# Motor_DC.net
KiCad netlist of a schematic drawn in Altium Designer
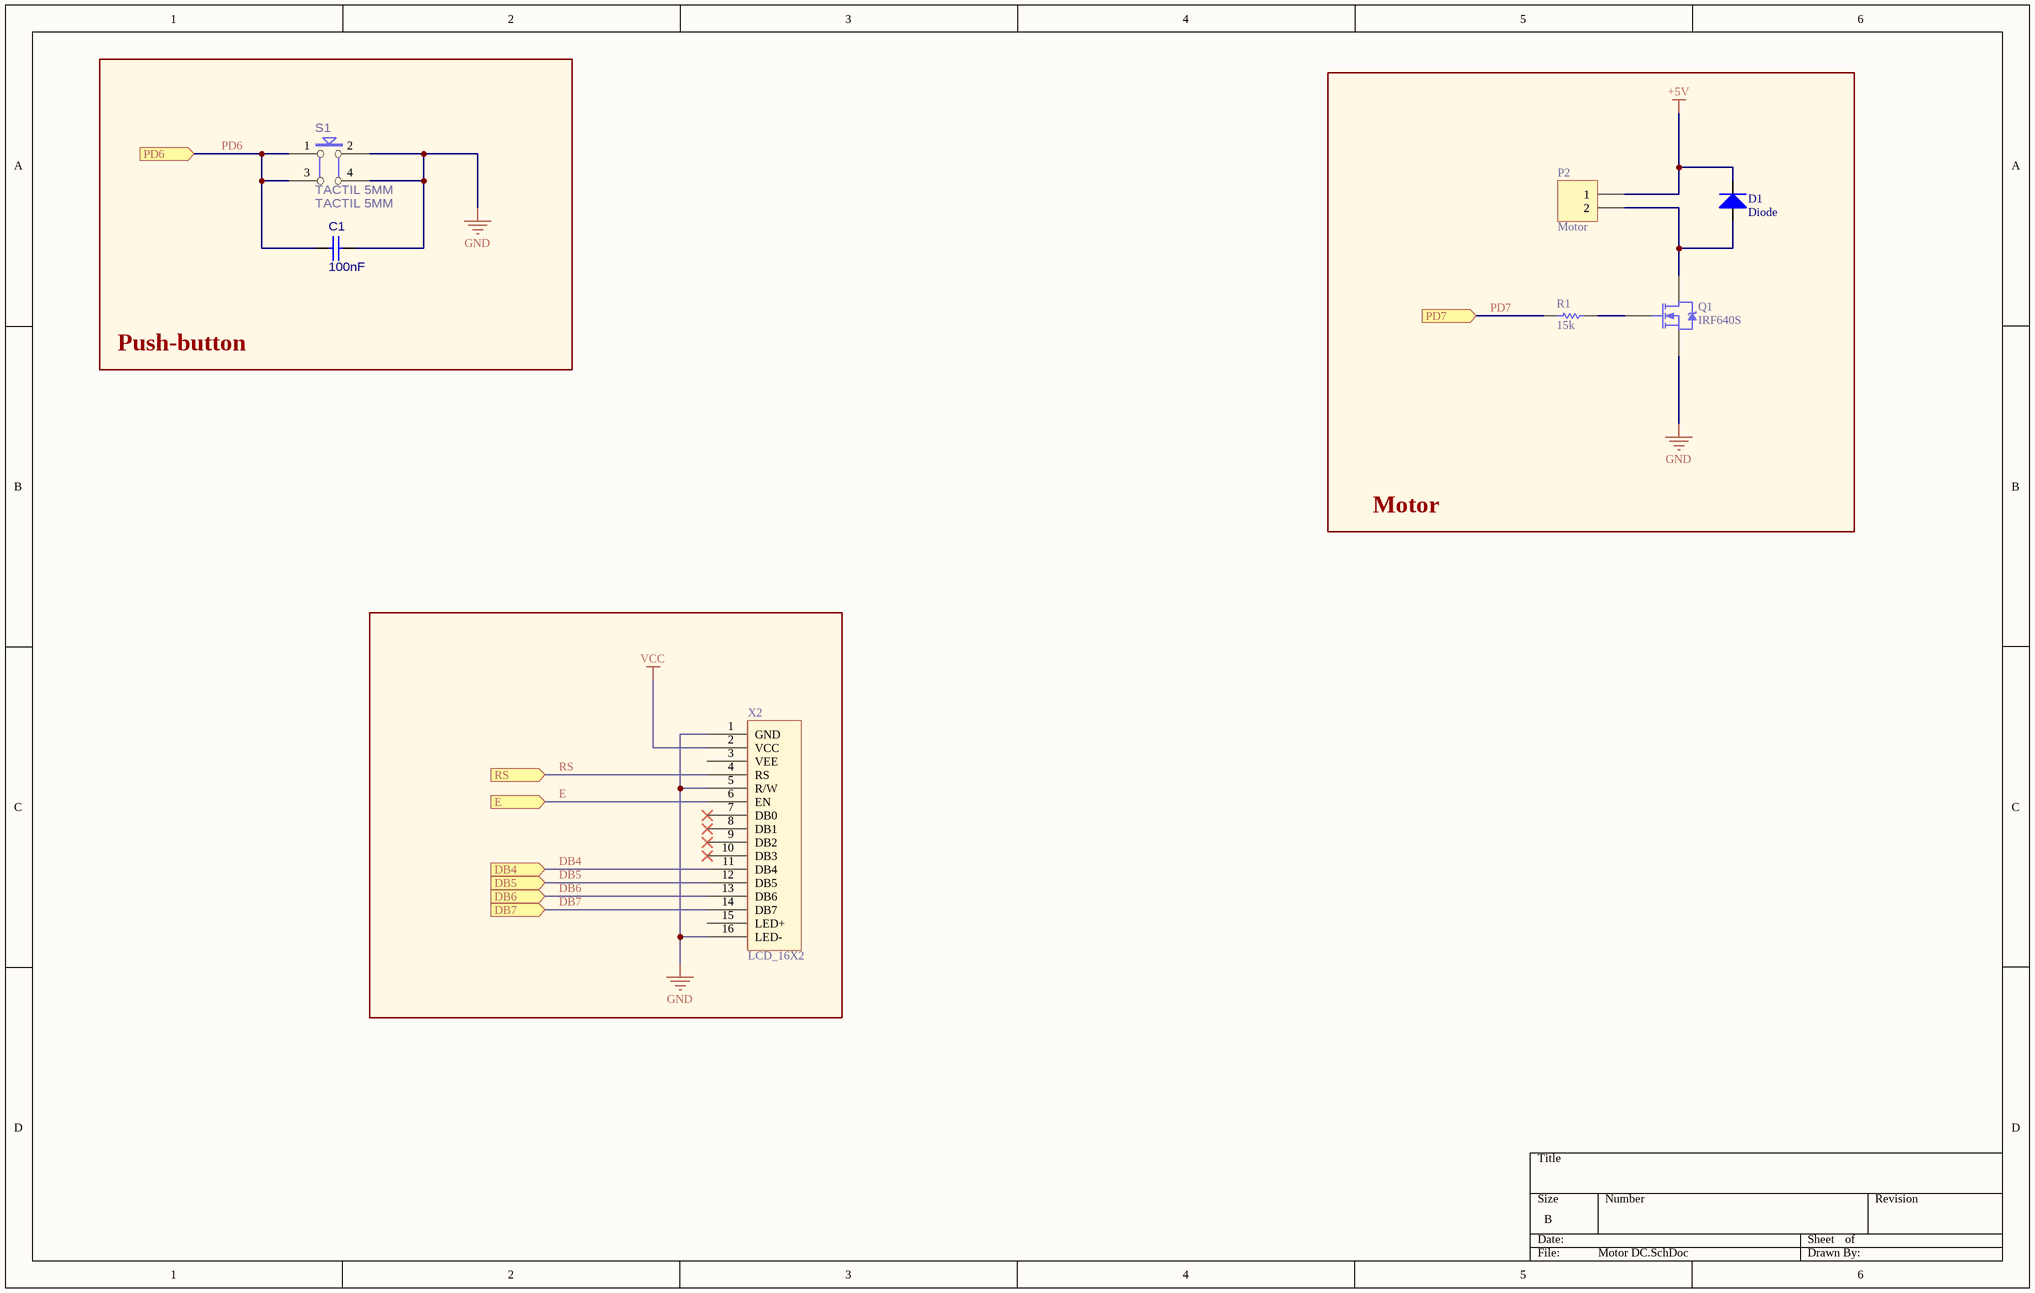
[diagram p0: Motor DC.SchDoc]

(export (version "E")
  (design (tool "Eeschema 10.0.6"))
  (components
    (comp (ref "C1")
      (value "100nF")
      (footprint "CAP_ELETR_16x25 - 90")
      (libsource (lib "Desafio_Hardware_Firmware_Nathania") (part "CAP_4"))
    )
    (comp (ref "D1")
      (value "Diode")
      (description "Default Diode")
      (libsource (lib "Desafio_Hardware_Firmware_Nathania") (part "Diode"))
    )
    (comp (ref "P2")
      (value "Motor")
      (footprint "HDR1X2")
      (description "Header, 2-Pin")
      (fields (field (name "PUBLISHER") "Altium Limited"))
      (libsource (lib "Miscellaneous Connectors") (part "Header 2"))
    )
    (comp (ref "Q1")
      (value "IRF640S")
      (footprint "D2PAK_N")
      (description "HEXFET N-Channel Power MOSFET")
      (fields (field (name "PUBLISHER") "Altium Limited"))
      (libsource (lib "Desafio_Hardware_Firmware_Nathania") (part "IRF640S"))
    )
    (comp (ref "R1")
      (value "15k")
      (footprint "RES0402")
      (description "Resistor")
      (libsource (lib "Desafio_Hardware_Firmware_Nathania") (part "Res1"))
    )
    (comp (ref "S1")
      (value "TACTIL 5MM")
      (footprint "TACTIL 5MM")
      (libsource (lib "Desafio_Hardware_Firmware_Nathania") (part "PUSH-BUTTON"))
    )
    (comp (ref "X2")
      (value "LCD_16X2")
      (footprint "LCD8X2")
      (libsource (lib "Desafio_Hardware_Firmware_Nathania") (part "LCD_16X2"))
    )
  )
  (nets
    (net (code "1") (name "+5V") (class "Default")
      (node (ref "D1") (pin "2") (pinfunction "K_2") (pintype "passive"))
      (node (ref "P2") (pin "1") (pinfunction "1_1") (pintype "passive"))
    )
    (net (code "2") (name "/DB4") (class "Default")
      (node (ref "X2") (pin "11") (pinfunction "DB4_11") (pintype "passive"))
    )
    (net (code "3") (name "/DB5") (class "Default")
      (node (ref "X2") (pin "12") (pinfunction "DB5_12") (pintype "passive"))
    )
    (net (code "4") (name "/DB6") (class "Default")
      (node (ref "X2") (pin "13") (pinfunction "DB6_13") (pintype "passive"))
    )
    (net (code "5") (name "/DB7") (class "Default")
      (node (ref "X2") (pin "14") (pinfunction "DB7_14") (pintype "passive"))
    )
    (net (code "6") (name "/E") (class "Default")
      (node (ref "X2") (pin "6") (pinfunction "EN_6") (pintype "passive"))
    )
    (net (code "7") (name "/PD6") (class "Default")
      (node (ref "C1") (pin "1") (pintype "passive"))
      (node (ref "S1") (pin "1") (pintype "passive"))
      (node (ref "S1") (pin "3") (pintype "passive"))
    )
    (net (code "8") (name "/PD7") (class "Default")
      (node (ref "R1") (pin "1") (pinfunction "1_1") (pintype "passive"))
    )
    (net (code "9") (name "/RS") (class "Default")
      (node (ref "X2") (pin "4") (pinfunction "RS_4") (pintype "passive"))
    )
    (net (code "10") (name "GND") (class "Default")
      (node (ref "C1") (pin "2") (pintype "passive"))
      (node (ref "Q1") (pin "3") (pinfunction "S_3") (pintype "passive"))
      (node (ref "S1") (pin "2") (pintype "passive"))
      (node (ref "S1") (pin "4") (pintype "passive"))
      (node (ref "X2") (pin "1") (pinfunction "GND_1") (pintype "passive"))
      (node (ref "X2") (pin "16") (pinfunction "LED-_16") (pintype "passive"))
      (node (ref "X2") (pin "5") (pinfunction "R/W_5") (pintype "passive"))
    )
    (net (code "11") (name "Net-(D1-A)") (class "Default")
      (node (ref "D1") (pin "1") (pinfunction "A_1") (pintype "passive"))
      (node (ref "P2") (pin "2") (pinfunction "2_2") (pintype "passive"))
      (node (ref "Q1") (pin "2") (pinfunction "D_2") (pintype "passive"))
    )
    (net (code "12") (name "Net-(Q1-G)") (class "Default")
      (node (ref "Q1") (pin "1") (pinfunction "G_1") (pintype "passive"))
      (node (ref "R1") (pin "2") (pinfunction "2_2") (pintype "passive"))
    )
    (net (code "13") (name "VCC") (class "Default")
      (node (ref "X2") (pin "2") (pinfunction "VCC_2") (pintype "passive"))
    )
    (net (code "14") (name "unconnected-(X2-DB0-Pad7)") (class "Default")
      (node (ref "X2") (pin "7") (pinfunction "DB0_7") (pintype "passive+no_connect"))
    )
    (net (code "15") (name "unconnected-(X2-DB1-Pad8)") (class "Default")
      (node (ref "X2") (pin "8") (pinfunction "DB1_8") (pintype "passive+no_connect"))
    )
    (net (code "16") (name "unconnected-(X2-DB2-Pad9)") (class "Default")
      (node (ref "X2") (pin "9") (pinfunction "DB2_9") (pintype "passive+no_connect"))
    )
    (net (code "17") (name "unconnected-(X2-DB3-Pad10)") (class "Default")
      (node (ref "X2") (pin "10") (pinfunction "DB3_10") (pintype "passive+no_connect"))
    )
    (net (code "18") (name "unconnected-(X2-LED+-Pad15)") (class "Default")
      (node (ref "X2") (pin "15") (pinfunction "LED+_15") (pintype "passive"))
    )
    (net (code "19") (name "unconnected-(X2-VEE-Pad3)") (class "Default")
      (node (ref "X2") (pin "3") (pinfunction "VEE_3") (pintype "passive"))
    )
  )
)
